# top_dsn.net
KiCad netlist of a schematic drawn in Altium Designer
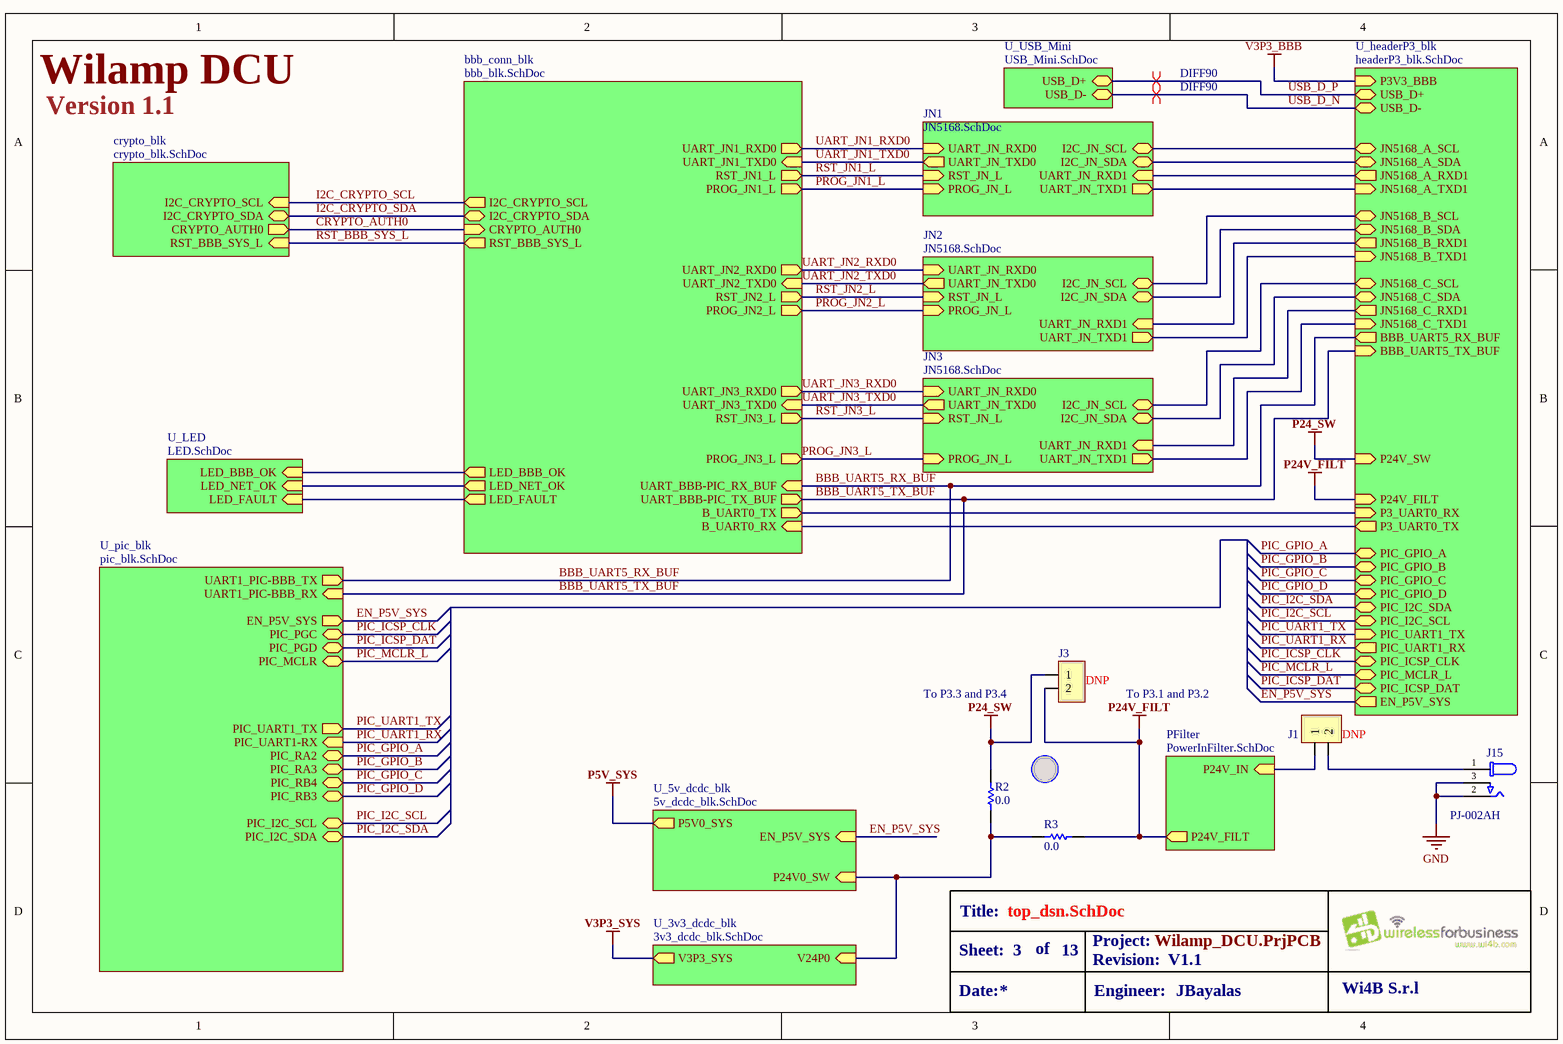
[diagram p0: top_dsn.SchDoc]

(export (version "E")
  (design (tool "Eeschema 10.0.6"))
  (components
    (comp (ref "J1")
      (value "*")
      (footprint "2pin 5mm Pitch")
      (fields (field (name "LOAD") "DNP"))
      (libsource (lib "Miscellaneous") (part "2PIN Signal 5mm Pitch"))
    )
    (comp (ref "J3")
      (value "*")
      (footprint "2pin 5mm Pitch")
      (fields (field (name "LOAD") "DNP"))
      (libsource (lib "") (part "2PIN Signal 5mm Pitch_1"))
    )
    (comp (ref "J15")
      (value "*")
      (footprint "PJ-002AH")
      (description "CONN PWR JACK 2.1X5.5MM HIGH CUR")
      (fields (field (name "MPN") "PJ-002AH"))
      (libsource (lib "Connector") (part "PJ-002AH"))
    )
    (comp (ref "R2")
      (value "0.0")
      (footprint "R0805")
      (description "RES SMD 0.0 OHM JUMPER 1/8W 0805")
      (fields (field (name "MPN") "RC0805JR-070RL"))
      (libsource (lib "Res") (part "RC0805JR-070RL"))
    )
    (comp (ref "R3")
      (value "0.0")
      (footprint "R0805")
      (description "RES SMD 0.0 OHM JUMPER 1/8W 0805")
      (fields (field (name "MPN") "RC0805JR-070RL"))
      (libsource (lib "Res") (part "RC0805JR-070RL"))
    )
  )
  (nets
    (net (code "21") (name "/P24V0_SW") (class "Default")
      (node (ref "R2") (pin "1") (pinfunction "1_1") (pintype "passive"))
      (node (ref "R3") (pin "1") (pinfunction "1_1") (pintype "passive"))
    )
    (net (code "22") (name "/P24V_IN") (class "Default")
      (node (ref "J1") (pin "1") (pinfunction "1_1") (pintype "passive"))
    )
    (net (code "52") (name "GND") (class "Default")
      (node (ref "J15") (pin "2") (pinfunction "2_2") (pintype "passive"))
      (node (ref "J15") (pin "3") (pinfunction "3_3") (pintype "passive"))
    )
    (net (code "53") (name "Net-(J1-Pad2)") (class "Default")
      (node (ref "J1") (pin "2") (pinfunction "2_2") (pintype "passive"))
      (node (ref "J15") (pin "1") (pinfunction "1_1") (pintype "passive"))
    )
    (net (code "55") (name "P24V_FILT") (class "Default")
      (node (ref "J3") (pin "2") (pinfunction "2_2") (pintype "passive"))
      (node (ref "R3") (pin "2") (pinfunction "2_2") (pintype "passive"))
    )
    (net (code "56") (name "P24_SW") (class "Default")
      (node (ref "J3") (pin "1") (pinfunction "1_1") (pintype "passive"))
      (node (ref "R2") (pin "2") (pinfunction "2_2") (pintype "passive"))
    )
  )
)
